# Rear_right_lamp_v2.net
KiCad netlist of a schematic drawn in EAGLE
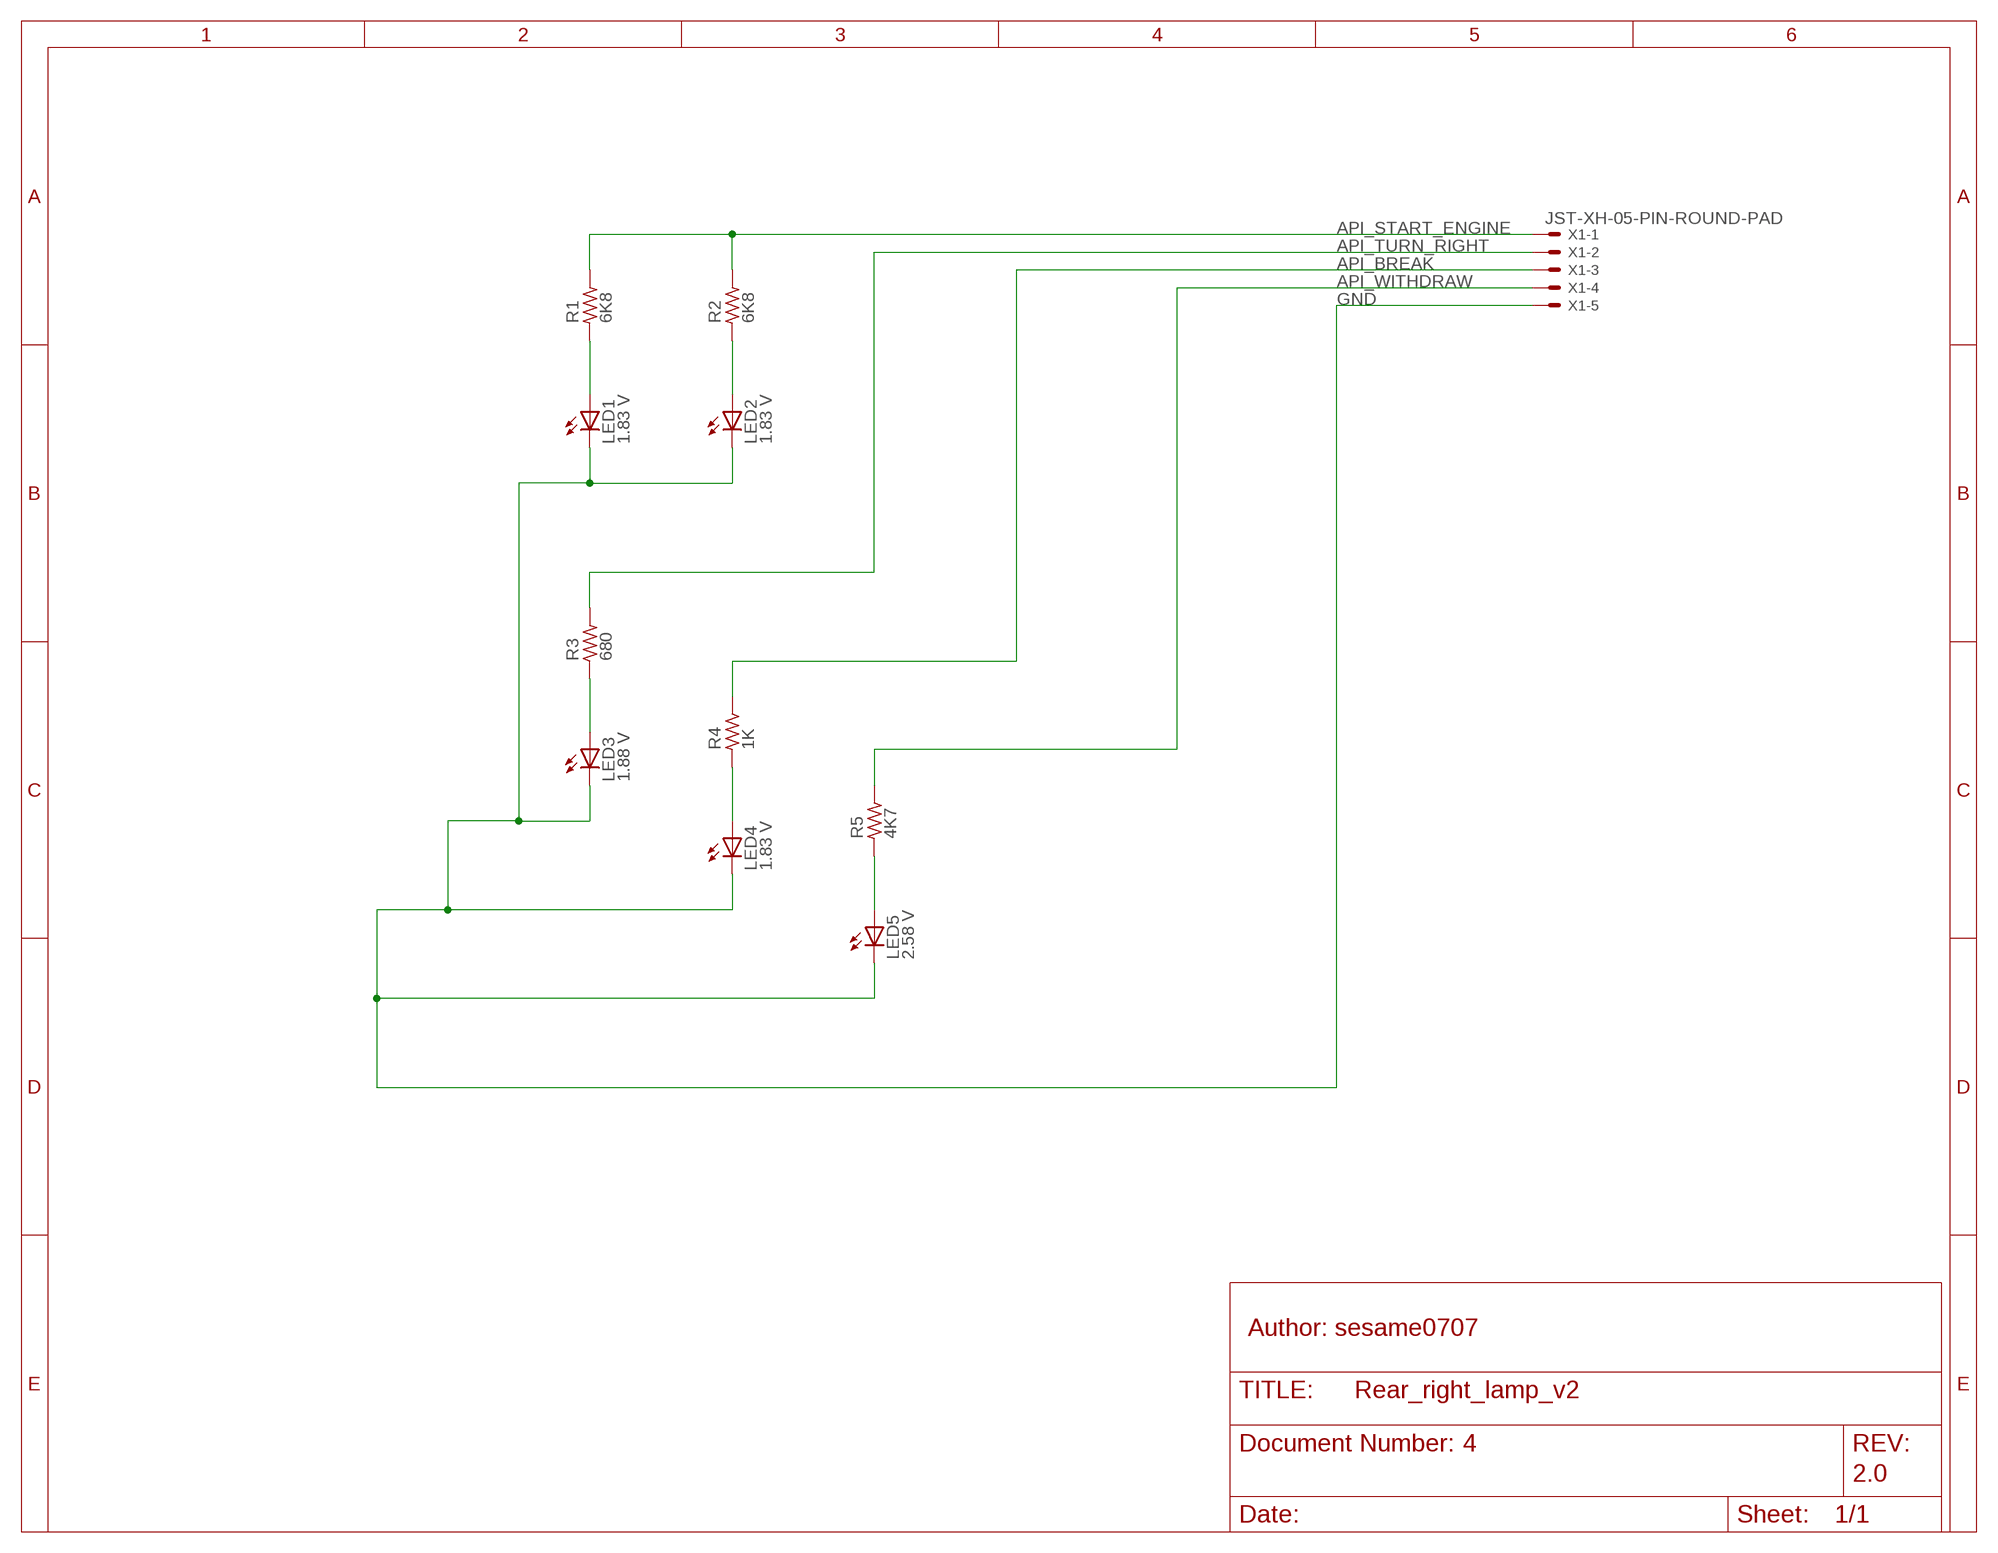
[diagram p0: schematic, sheet 1]

(export (version "E")
  (design (tool "Eeschema 10.0.6"))
  (components
    (comp (ref "LED1")
      (value "1.83 V")
      (footprint "eagle-import:LED5MM")
      (libsource (lib "eagle-import") (part "LED5MM"))
    )
    (comp (ref "LED2")
      (value "1.83 V")
      (footprint "eagle-import:LED5MM")
      (libsource (lib "eagle-import") (part "LED5MM"))
    )
    (comp (ref "LED3")
      (value "1.88 V")
      (footprint "eagle-import:LED5MM")
      (libsource (lib "eagle-import") (part "LED5MM"))
    )
    (comp (ref "LED4")
      (value "1.83 V")
      (footprint "eagle-import:LED5MM")
      (libsource (lib "eagle-import") (part "LED5MM"))
    )
    (comp (ref "LED5")
      (value "2.58 V")
      (footprint "eagle-import:LED5MM")
      (libsource (lib "eagle-import") (part "LED5MM"))
    )
    (comp (ref "R1")
      (value "6K8")
      (footprint "eagle-import:R0805")
      (libsource (lib "eagle-import") (part "R_0805"))
    )
    (comp (ref "R2")
      (value "6K8")
      (footprint "eagle-import:R0805")
      (libsource (lib "eagle-import") (part "R_0805"))
    )
    (comp (ref "R3")
      (value "680")
      (footprint "eagle-import:R0805")
      (libsource (lib "eagle-import") (part "R_0805"))
    )
    (comp (ref "R4")
      (value "1K")
      (footprint "eagle-import:R0805")
      (libsource (lib "eagle-import") (part "R_0805"))
    )
    (comp (ref "R5")
      (value "4K7")
      (footprint "eagle-import:R0805")
      (libsource (lib "eagle-import") (part "R_0805"))
    )
    (comp (ref "X1")
      (value "JST-XH-05-PIN-ROUND-PAD")
      (footprint "eagle-import:JST-XH-05-PACKAGE-ROUND-PAD")
      (libsource (lib "eagle-import") (part "JST-XH-05-PIN-ROUND-PAD"))
    )
  )
  (nets
    (net (code "1") (name "/API_BREAK") (class "Default")
      (node (ref "R4") (pin "2") (pinfunction "2_2") (pintype "passive"))
      (node (ref "X1") (pin "3") (pinfunction "S_3") (pintype "passive"))
    )
    (net (code "2") (name "/API_START_ENGINE") (class "Default")
      (node (ref "R1") (pin "2") (pinfunction "2_2") (pintype "passive"))
      (node (ref "R2") (pin "2") (pinfunction "2_2") (pintype "passive"))
      (node (ref "X1") (pin "1") (pinfunction "S_1") (pintype "passive"))
    )
    (net (code "3") (name "/API_TURN_RIGHT") (class "Default")
      (node (ref "R3") (pin "2") (pinfunction "2_2") (pintype "passive"))
      (node (ref "X1") (pin "2") (pinfunction "S_2") (pintype "passive"))
    )
    (net (code "4") (name "/API_WITHDRAW") (class "Default")
      (node (ref "R5") (pin "2") (pinfunction "2_2") (pintype "passive"))
      (node (ref "X1") (pin "4") (pinfunction "S_4") (pintype "passive"))
    )
    (net (code "5") (name "/GND") (class "Default")
      (node (ref "LED1") (pin "K") (pinfunction "C_K") (pintype "passive"))
      (node (ref "LED2") (pin "K") (pinfunction "C_K") (pintype "passive"))
      (node (ref "LED3") (pin "K") (pinfunction "C_K") (pintype "passive"))
      (node (ref "LED4") (pin "K") (pinfunction "C_K") (pintype "passive"))
      (node (ref "LED5") (pin "K") (pinfunction "C_K") (pintype "passive"))
      (node (ref "X1") (pin "5") (pinfunction "S_5") (pintype "passive"))
    )
    (net (code "6") (name "Net-(LED1-PadA)") (class "Default")
      (node (ref "LED1") (pin "A") (pinfunction "A_A") (pintype "passive"))
      (node (ref "R1") (pin "1") (pinfunction "1_1") (pintype "passive"))
    )
    (net (code "7") (name "Net-(LED2-PadA)") (class "Default")
      (node (ref "LED2") (pin "A") (pinfunction "A_A") (pintype "passive"))
      (node (ref "R2") (pin "1") (pinfunction "1_1") (pintype "passive"))
    )
    (net (code "8") (name "Net-(LED3-PadA)") (class "Default")
      (node (ref "LED3") (pin "A") (pinfunction "A_A") (pintype "passive"))
      (node (ref "R3") (pin "1") (pinfunction "1_1") (pintype "passive"))
    )
    (net (code "9") (name "Net-(LED4-PadA)") (class "Default")
      (node (ref "LED4") (pin "A") (pinfunction "A_A") (pintype "passive"))
      (node (ref "R4") (pin "1") (pinfunction "1_1") (pintype "passive"))
    )
    (net (code "10") (name "Net-(LED5-PadA)") (class "Default")
      (node (ref "LED5") (pin "A") (pinfunction "A_A") (pintype "passive"))
      (node (ref "R5") (pin "1") (pinfunction "1_1") (pintype "passive"))
    )
  )
)
